# pico_camera.net
KiCad netlist of a schematic drawn in Altium Designer
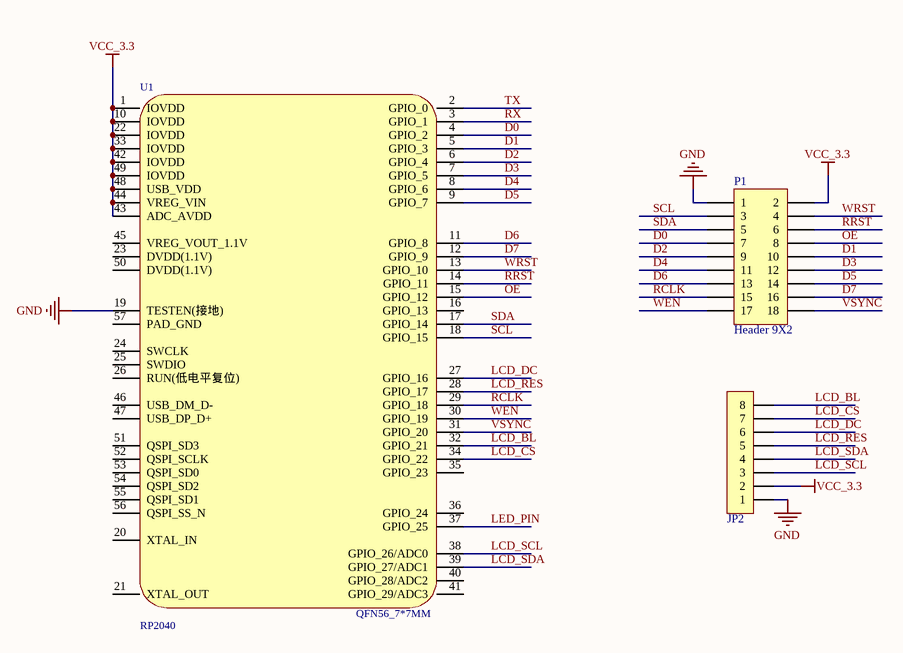
[diagram p0: pico_camera.SchDoc]

(export (version "E")
  (design (tool "Eeschema 10.0.6"))
  (components
    (comp (ref "JP2")
      (value "HDR-1X8")
      (footprint "XH2.54-WI-8P")
      (description "8P接插件")
      (fields (field (name "版权归属") "封装库来自淘宝 ID：黄晶宝石"))
      (libsource (lib "5.4 - 接插件-脚距2.54 (100mil) ") (part "Header 8"))
    )
    (comp (ref "P1")
      (value "Header 9X2")
      (footprint "HDR2X9")
      (description "Header, 9-Pin, Dual row")
      (fields (field (name "PUBLISHER") "Altium Limited"))
      (libsource (lib "ATK-OV7725") (part "Header 9X2"))
    )
    (comp (ref "U1")
      (value "QFN56_7*7MM")
      (footprint "QFN_56_7*7MM")
      (fields (field (name "COMMENT_1") "RP2040"))
      (libsource (lib "InfineonRadar") (part "RP2040"))
    )
  )
  (nets
    (net (code "1") (name "/D0") (class "Default")
      (node (ref "P1") (pin "7") (pinfunction "7_7") (pintype "passive"))
      (node (ref "U1") (pin "4") (pinfunction "GPIO_2_4") (pintype "passive"))
    )
    (net (code "2") (name "/D1") (class "Default")
      (node (ref "P1") (pin "10") (pinfunction "10_10") (pintype "passive"))
      (node (ref "U1") (pin "5") (pinfunction "GPIO_3_5") (pintype "passive"))
    )
    (net (code "3") (name "/D2") (class "Default")
      (node (ref "P1") (pin "9") (pinfunction "9_9") (pintype "passive"))
      (node (ref "U1") (pin "6") (pinfunction "GPIO_4_6") (pintype "passive"))
    )
    (net (code "4") (name "/D3") (class "Default")
      (node (ref "P1") (pin "12") (pinfunction "12_12") (pintype "passive"))
      (node (ref "U1") (pin "7") (pinfunction "GPIO_5_7") (pintype "passive"))
    )
    (net (code "5") (name "/D4") (class "Default")
      (node (ref "P1") (pin "11") (pinfunction "11_11") (pintype "passive"))
      (node (ref "U1") (pin "8") (pinfunction "GPIO_6_8") (pintype "passive"))
    )
    (net (code "6") (name "/D5") (class "Default")
      (node (ref "P1") (pin "14") (pinfunction "14_14") (pintype "passive"))
      (node (ref "U1") (pin "9") (pinfunction "GPIO_7_9") (pintype "passive"))
    )
    (net (code "7") (name "/D6") (class "Default")
      (node (ref "P1") (pin "13") (pinfunction "13_13") (pintype "passive"))
      (node (ref "U1") (pin "11") (pinfunction "GPIO_8_11") (pintype "passive"))
    )
    (net (code "8") (name "/D7") (class "Default")
      (node (ref "P1") (pin "16") (pinfunction "16_16") (pintype "passive"))
      (node (ref "U1") (pin "12") (pinfunction "GPIO_9_12") (pintype "passive"))
    )
    (net (code "9") (name "/LCD_BL") (class "Default")
      (node (ref "JP2") (pin "8") (pinfunction "8_8") (pintype "passive"))
      (node (ref "U1") (pin "32") (pinfunction "GPIO_21_32") (pintype "passive"))
    )
    (net (code "10") (name "/LCD_CS") (class "Default")
      (node (ref "JP2") (pin "7") (pinfunction "7_7") (pintype "passive"))
      (node (ref "U1") (pin "34") (pinfunction "GPIO_22_34") (pintype "passive"))
    )
    (net (code "11") (name "/LCD_DC") (class "Default")
      (node (ref "JP2") (pin "6") (pinfunction "6_6") (pintype "passive"))
      (node (ref "U1") (pin "27") (pinfunction "GPIO_16_27") (pintype "passive"))
    )
    (net (code "12") (name "/LCD_RES") (class "Default")
      (node (ref "JP2") (pin "5") (pinfunction "5_5") (pintype "passive"))
      (node (ref "U1") (pin "28") (pinfunction "GPIO_17_28") (pintype "passive"))
    )
    (net (code "13") (name "/LCD_SCL") (class "Default")
      (node (ref "JP2") (pin "3") (pinfunction "3_3") (pintype "passive"))
      (node (ref "U1") (pin "38") (pinfunction "GPIO_26/ADC0_38") (pintype "passive"))
    )
    (net (code "14") (name "/LCD_SDA") (class "Default")
      (node (ref "JP2") (pin "4") (pinfunction "4_4") (pintype "passive"))
      (node (ref "U1") (pin "39") (pinfunction "GPIO_27/ADC1_39") (pintype "passive"))
    )
    (net (code "15") (name "/LED_PIN") (class "Default")
      (node (ref "U1") (pin "37") (pinfunction "GPIO_25_37") (pintype "passive"))
    )
    (net (code "16") (name "/OE") (class "Default")
      (node (ref "P1") (pin "8") (pinfunction "8_8") (pintype "passive"))
      (node (ref "U1") (pin "15") (pinfunction "GPIO_12_15") (pintype "passive"))
    )
    (net (code "17") (name "/RCLK") (class "Default")
      (node (ref "P1") (pin "15") (pinfunction "15_15") (pintype "passive"))
      (node (ref "U1") (pin "29") (pinfunction "GPIO_18_29") (pintype "passive"))
    )
    (net (code "18") (name "/RRST") (class "Default")
      (node (ref "P1") (pin "6") (pinfunction "6_6") (pintype "passive"))
      (node (ref "U1") (pin "14") (pinfunction "GPIO_11_14") (pintype "passive"))
    )
    (net (code "19") (name "/RX") (class "Default")
      (node (ref "U1") (pin "3") (pinfunction "GPIO_1_3") (pintype "passive"))
    )
    (net (code "20") (name "/SCL") (class "Default")
      (node (ref "P1") (pin "3") (pinfunction "3_3") (pintype "passive"))
      (node (ref "U1") (pin "18") (pinfunction "GPIO_15_18") (pintype "passive"))
    )
    (net (code "21") (name "/SDA") (class "Default")
      (node (ref "P1") (pin "5") (pinfunction "5_5") (pintype "passive"))
      (node (ref "U1") (pin "17") (pinfunction "GPIO_14_17") (pintype "passive"))
    )
    (net (code "22") (name "/TX") (class "Default")
      (node (ref "U1") (pin "2") (pinfunction "GPIO_0_2") (pintype "passive"))
    )
    (net (code "23") (name "/VSYNC") (class "Default")
      (node (ref "P1") (pin "18") (pinfunction "18_18") (pintype "passive"))
      (node (ref "U1") (pin "31") (pinfunction "GPIO_20_31") (pintype "passive"))
    )
    (net (code "24") (name "/WEN") (class "Default")
      (node (ref "P1") (pin "17") (pinfunction "17_17") (pintype "passive"))
      (node (ref "U1") (pin "30") (pinfunction "GPIO_19_30") (pintype "passive"))
    )
    (net (code "25") (name "/WRST") (class "Default")
      (node (ref "P1") (pin "4") (pinfunction "4_4") (pintype "passive"))
      (node (ref "U1") (pin "13") (pinfunction "GPIO_10_13") (pintype "passive"))
    )
    (net (code "26") (name "GND") (class "Default")
      (node (ref "JP2") (pin "1") (pinfunction "1_1") (pintype "passive"))
      (node (ref "P1") (pin "1") (pinfunction "1_1") (pintype "passive"))
      (node (ref "U1") (pin "19") (pinfunction "TESTEN(接地)_19") (pintype "passive"))
    )
    (net (code "27") (name "VCC_3.3") (class "Default")
      (node (ref "JP2") (pin "2") (pinfunction "2_2") (pintype "passive"))
      (node (ref "P1") (pin "2") (pinfunction "2_2") (pintype "passive"))
      (node (ref "U1") (pin "1") (pinfunction "IOVDD_1") (pintype "passive"))
      (node (ref "U1") (pin "10") (pinfunction "IOVDD_10") (pintype "passive"))
      (node (ref "U1") (pin "22") (pinfunction "IOVDD_22") (pintype "passive"))
      (node (ref "U1") (pin "33") (pinfunction "IOVDD_33") (pintype "passive"))
      (node (ref "U1") (pin "42") (pinfunction "IOVDD_42") (pintype "passive"))
      (node (ref "U1") (pin "43") (pinfunction "ADC_AVDD_43") (pintype "passive"))
      (node (ref "U1") (pin "44") (pinfunction "VREG_VIN_44") (pintype "passive"))
      (node (ref "U1") (pin "48") (pinfunction "USB_VDD_48") (pintype "passive"))
      (node (ref "U1") (pin "49") (pinfunction "IOVDD_49") (pintype "passive"))
    )
    (net (code "28") (name "unconnected-(U1-DVDD(1.1V)-Pad23)") (class "Default")
      (node (ref "U1") (pin "23") (pinfunction "DVDD(1.1V)_23") (pintype "passive"))
    )
    (net (code "29") (name "unconnected-(U1-DVDD(1.1V)-Pad50)") (class "Default")
      (node (ref "U1") (pin "50") (pinfunction "DVDD(1.1V)_50") (pintype "passive"))
    )
    (net (code "30") (name "unconnected-(U1-GPIO_13-Pad16)") (class "Default")
      (node (ref "U1") (pin "16") (pinfunction "GPIO_13_16") (pintype "passive"))
    )
    (net (code "31") (name "unconnected-(U1-GPIO_23-Pad35)") (class "Default")
      (node (ref "U1") (pin "35") (pinfunction "GPIO_23_35") (pintype "passive"))
    )
    (net (code "32") (name "unconnected-(U1-GPIO_24-Pad36)") (class "Default")
      (node (ref "U1") (pin "36") (pinfunction "GPIO_24_36") (pintype "passive"))
    )
    (net (code "33") (name "unconnected-(U1-GPIO_28{slash}ADC2-Pad40)") (class "Default")
      (node (ref "U1") (pin "40") (pinfunction "GPIO_28/ADC2_40") (pintype "passive"))
    )
    (net (code "34") (name "unconnected-(U1-GPIO_29{slash}ADC3-Pad41)") (class "Default")
      (node (ref "U1") (pin "41") (pinfunction "GPIO_29/ADC3_41") (pintype "passive"))
    )
    (net (code "35") (name "unconnected-(U1-PAD_GND-Pad57)") (class "Default")
      (node (ref "U1") (pin "57") (pinfunction "PAD_GND_57") (pintype "passive"))
    )
    (net (code "36") (name "unconnected-(U1-QSPI_SCLK-Pad52)") (class "Default")
      (node (ref "U1") (pin "52") (pinfunction "QSPI_SCLK_52") (pintype "passive"))
    )
    (net (code "37") (name "unconnected-(U1-QSPI_SD0-Pad53)") (class "Default")
      (node (ref "U1") (pin "53") (pinfunction "QSPI_SD0_53") (pintype "passive"))
    )
    (net (code "38") (name "unconnected-(U1-QSPI_SD1-Pad55)") (class "Default")
      (node (ref "U1") (pin "55") (pinfunction "QSPI_SD1_55") (pintype "passive"))
    )
    (net (code "39") (name "unconnected-(U1-QSPI_SD2-Pad54)") (class "Default")
      (node (ref "U1") (pin "54") (pinfunction "QSPI_SD2_54") (pintype "passive"))
    )
    (net (code "40") (name "unconnected-(U1-QSPI_SD3-Pad51)") (class "Default")
      (node (ref "U1") (pin "51") (pinfunction "QSPI_SD3_51") (pintype "passive"))
    )
    (net (code "41") (name "unconnected-(U1-QSPI_SS_N-Pad56)") (class "Default")
      (node (ref "U1") (pin "56") (pinfunction "QSPI_SS_N_56") (pintype "passive"))
    )
    (net (code "42") (name "unconnected-(U1-RUN(低电平复位)-Pad26)") (class "Default")
      (node (ref "U1") (pin "26") (pinfunction "RUN(低电平复位)_26") (pintype "passive"))
    )
    (net (code "43") (name "unconnected-(U1-SWCLK-Pad24)") (class "Default")
      (node (ref "U1") (pin "24") (pinfunction "SWCLK_24") (pintype "passive"))
    )
    (net (code "44") (name "unconnected-(U1-SWDIO-Pad25)") (class "Default")
      (node (ref "U1") (pin "25") (pinfunction "SWDIO_25") (pintype "passive"))
    )
    (net (code "45") (name "unconnected-(U1-USB_DM_D--Pad46)") (class "Default")
      (node (ref "U1") (pin "46") (pinfunction "USB_DM_D-_46") (pintype "passive"))
    )
    (net (code "46") (name "unconnected-(U1-USB_DP_D+-Pad47)") (class "Default")
      (node (ref "U1") (pin "47") (pinfunction "USB_DP_D+_47") (pintype "passive"))
    )
    (net (code "47") (name "unconnected-(U1-VREG_VOUT_1.1V-Pad45)") (class "Default")
      (node (ref "U1") (pin "45") (pinfunction "VREG_VOUT_1.1V_45") (pintype "passive"))
    )
    (net (code "48") (name "unconnected-(U1-XTAL_IN-Pad20)") (class "Default")
      (node (ref "U1") (pin "20") (pinfunction "XTAL_IN_20") (pintype "passive"))
    )
    (net (code "49") (name "unconnected-(U1-XTAL_OUT-Pad21)") (class "Default")
      (node (ref "U1") (pin "21") (pinfunction "XTAL_OUT_21") (pintype "passive"))
    )
  )
)
